# Digital.net
KiCad netlist of a schematic drawn in Altium Designer
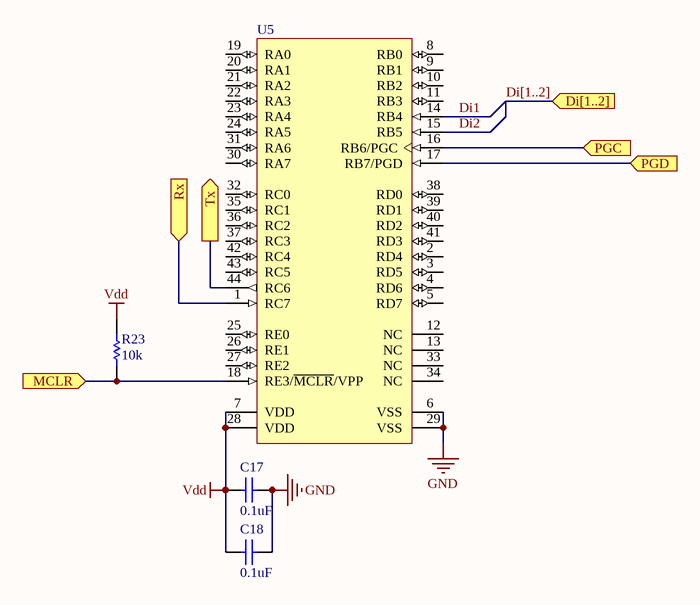
[diagram p0: Digital.SchDoc]

(export (version "E")
  (design (tool "Eeschema 10.0.6"))
  (components
    (comp (ref "C17")
      (value "0.1uF")
      (footprint "C0805")
      (description "Capacitor")
      (fields (field (name "Comment") "Cap") (field (name "PUBLISHER") "Altium Limited"))
      (libsource (lib "Miscellaneous Devices") (part "Cap"))
    )
    (comp (ref "C18")
      (value "0.1uF")
      (footprint "C0805")
      (description "Capacitor")
      (fields (field (name "Comment") "Cap") (field (name "PUBLISHER") "Altium Limited"))
      (libsource (lib "Miscellaneous Devices") (part "Cap"))
    )
    (comp (ref "R23")
      (value "10k")
      (footprint "C1206")
      (description "Resistor")
      (fields (field (name "Comment") "Res1") (field (name "PUBLISHER") "Altium Limited"))
      (libsource (lib "Miscellaneous Devices") (part "Res1"))
    )
    (comp (ref "U5")
      (value "MYON")
      (footprint "MCHP-TQFP-PT44_N")
      (fields (field (name "MANUFACTURER") "Microchip") (field (name "PARTNUMBER") "PIC18F46K22-I/PT"))
      (libsource (lib "Microchip PIC18") (part "PIC18F46K22-I/PT"))
    )
  )
  (nets
    (net (code "1") (name "/Di1") (class "Default")
      (node (ref "U5") (pin "14") (pinfunction "RB4_14") (pintype "input"))
    )
    (net (code "2") (name "/Di2") (class "Default")
      (node (ref "U5") (pin "15") (pinfunction "RB5_15") (pintype "input"))
    )
    (net (code "4") (name "/MCLR") (class "Default")
      (node (ref "R23") (pin "2") (pinfunction "2_2") (pintype "passive"))
      (node (ref "U5") (pin "18") (pinfunction "RE3/~{MCLR}/VPP_18") (pintype "input"))
    )
    (net (code "5") (name "/PGC") (class "Default")
      (node (ref "U5") (pin "16") (pinfunction "RB6/PGC_16") (pintype "input"))
    )
    (net (code "6") (name "/PGD") (class "Default")
      (node (ref "U5") (pin "17") (pinfunction "RB7/PGD_17") (pintype "input"))
    )
    (net (code "7") (name "/Rx") (class "Default")
      (node (ref "U5") (pin "1") (pinfunction "RC7_1") (pintype "input"))
    )
    (net (code "8") (name "/Tx") (class "Default")
      (node (ref "U5") (pin "44") (pinfunction "RC6_44") (pintype "output"))
    )
    (net (code "9") (name "GND") (class "Default")
      (node (ref "C17") (pin "1") (pinfunction "1_1") (pintype "passive"))
      (node (ref "C18") (pin "1") (pinfunction "1_1") (pintype "passive"))
      (node (ref "U5") (pin "29") (pinfunction "VSS_29") (pintype "power_in"))
      (node (ref "U5") (pin "6") (pinfunction "VSS_6") (pintype "power_in"))
    )
    (net (code "10") (name "Vdd") (class "Default")
      (node (ref "C17") (pin "2") (pinfunction "2_2") (pintype "passive"))
      (node (ref "C18") (pin "2") (pinfunction "2_2") (pintype "passive"))
      (node (ref "R23") (pin "1") (pinfunction "1_1") (pintype "passive"))
      (node (ref "U5") (pin "28") (pinfunction "VDD_28") (pintype "power_in"))
      (node (ref "U5") (pin "7") (pinfunction "VDD_7") (pintype "power_in"))
    )
    (net (code "11") (name "unconnected-(U5-NC-Pad12)") (class "Default")
      (node (ref "U5") (pin "12") (pinfunction "NC_12") (pintype "passive"))
    )
    (net (code "12") (name "unconnected-(U5-NC-Pad13)") (class "Default")
      (node (ref "U5") (pin "13") (pinfunction "NC_13") (pintype "passive"))
    )
    (net (code "13") (name "unconnected-(U5-NC-Pad33)") (class "Default")
      (node (ref "U5") (pin "33") (pinfunction "NC_33") (pintype "passive"))
    )
    (net (code "14") (name "unconnected-(U5-NC-Pad34)") (class "Default")
      (node (ref "U5") (pin "34") (pinfunction "NC_34") (pintype "passive"))
    )
    (net (code "15") (name "unconnected-(U5-RA0-Pad19)") (class "Default")
      (node (ref "U5") (pin "19") (pinfunction "RA0_19") (pintype "bidirectional"))
    )
    (net (code "16") (name "unconnected-(U5-RA1-Pad20)") (class "Default")
      (node (ref "U5") (pin "20") (pinfunction "RA1_20") (pintype "bidirectional"))
    )
    (net (code "17") (name "unconnected-(U5-RA2-Pad21)") (class "Default")
      (node (ref "U5") (pin "21") (pinfunction "RA2_21") (pintype "bidirectional"))
    )
    (net (code "18") (name "unconnected-(U5-RA3-Pad22)") (class "Default")
      (node (ref "U5") (pin "22") (pinfunction "RA3_22") (pintype "bidirectional"))
    )
    (net (code "19") (name "unconnected-(U5-RA4-Pad23)") (class "Default")
      (node (ref "U5") (pin "23") (pinfunction "RA4_23") (pintype "bidirectional"))
    )
    (net (code "20") (name "unconnected-(U5-RA5-Pad24)") (class "Default")
      (node (ref "U5") (pin "24") (pinfunction "RA5_24") (pintype "bidirectional"))
    )
    (net (code "21") (name "unconnected-(U5-RA6-Pad31)") (class "Default")
      (node (ref "U5") (pin "31") (pinfunction "RA6_31") (pintype "bidirectional"))
    )
    (net (code "22") (name "unconnected-(U5-RA7-Pad30)") (class "Default")
      (node (ref "U5") (pin "30") (pinfunction "RA7_30") (pintype "bidirectional"))
    )
    (net (code "23") (name "unconnected-(U5-RB0-Pad8)") (class "Default")
      (node (ref "U5") (pin "8") (pinfunction "RB0_8") (pintype "bidirectional"))
    )
    (net (code "24") (name "unconnected-(U5-RB1-Pad9)") (class "Default")
      (node (ref "U5") (pin "9") (pinfunction "RB1_9") (pintype "bidirectional"))
    )
    (net (code "25") (name "unconnected-(U5-RB2-Pad10)") (class "Default")
      (node (ref "U5") (pin "10") (pinfunction "RB2_10") (pintype "bidirectional"))
    )
    (net (code "26") (name "unconnected-(U5-RB3-Pad11)") (class "Default")
      (node (ref "U5") (pin "11") (pinfunction "RB3_11") (pintype "bidirectional"))
    )
    (net (code "27") (name "unconnected-(U5-RC0-Pad32)") (class "Default")
      (node (ref "U5") (pin "32") (pinfunction "RC0_32") (pintype "bidirectional"))
    )
    (net (code "28") (name "unconnected-(U5-RC1-Pad35)") (class "Default")
      (node (ref "U5") (pin "35") (pinfunction "RC1_35") (pintype "bidirectional"))
    )
    (net (code "29") (name "unconnected-(U5-RC2-Pad36)") (class "Default")
      (node (ref "U5") (pin "36") (pinfunction "RC2_36") (pintype "bidirectional"))
    )
    (net (code "30") (name "unconnected-(U5-RC3-Pad37)") (class "Default")
      (node (ref "U5") (pin "37") (pinfunction "RC3_37") (pintype "bidirectional"))
    )
    (net (code "31") (name "unconnected-(U5-RC4-Pad42)") (class "Default")
      (node (ref "U5") (pin "42") (pinfunction "RC4_42") (pintype "bidirectional"))
    )
    (net (code "32") (name "unconnected-(U5-RC5-Pad43)") (class "Default")
      (node (ref "U5") (pin "43") (pinfunction "RC5_43") (pintype "bidirectional"))
    )
    (net (code "33") (name "unconnected-(U5-RD0-Pad38)") (class "Default")
      (node (ref "U5") (pin "38") (pinfunction "RD0_38") (pintype "bidirectional"))
    )
    (net (code "34") (name "unconnected-(U5-RD1-Pad39)") (class "Default")
      (node (ref "U5") (pin "39") (pinfunction "RD1_39") (pintype "bidirectional"))
    )
    (net (code "35") (name "unconnected-(U5-RD2-Pad40)") (class "Default")
      (node (ref "U5") (pin "40") (pinfunction "RD2_40") (pintype "bidirectional"))
    )
    (net (code "36") (name "unconnected-(U5-RD3-Pad41)") (class "Default")
      (node (ref "U5") (pin "41") (pinfunction "RD3_41") (pintype "bidirectional"))
    )
    (net (code "37") (name "unconnected-(U5-RD4-Pad2)") (class "Default")
      (node (ref "U5") (pin "2") (pinfunction "RD4_2") (pintype "bidirectional"))
    )
    (net (code "38") (name "unconnected-(U5-RD5-Pad3)") (class "Default")
      (node (ref "U5") (pin "3") (pinfunction "RD5_3") (pintype "bidirectional"))
    )
    (net (code "39") (name "unconnected-(U5-RD6-Pad4)") (class "Default")
      (node (ref "U5") (pin "4") (pinfunction "RD6_4") (pintype "bidirectional"))
    )
    (net (code "40") (name "unconnected-(U5-RD7-Pad5)") (class "Default")
      (node (ref "U5") (pin "5") (pinfunction "RD7_5") (pintype "bidirectional"))
    )
    (net (code "41") (name "unconnected-(U5-RE0-Pad25)") (class "Default")
      (node (ref "U5") (pin "25") (pinfunction "RE0_25") (pintype "bidirectional"))
    )
    (net (code "42") (name "unconnected-(U5-RE1-Pad26)") (class "Default")
      (node (ref "U5") (pin "26") (pinfunction "RE1_26") (pintype "bidirectional"))
    )
    (net (code "43") (name "unconnected-(U5-RE2-Pad27)") (class "Default")
      (node (ref "U5") (pin "27") (pinfunction "RE2_27") (pintype "bidirectional"))
    )
  )
)
